# Wheel_Encoder_Adapter_Schmitt_555.net
KiCad netlist of a schematic drawn in EAGLE
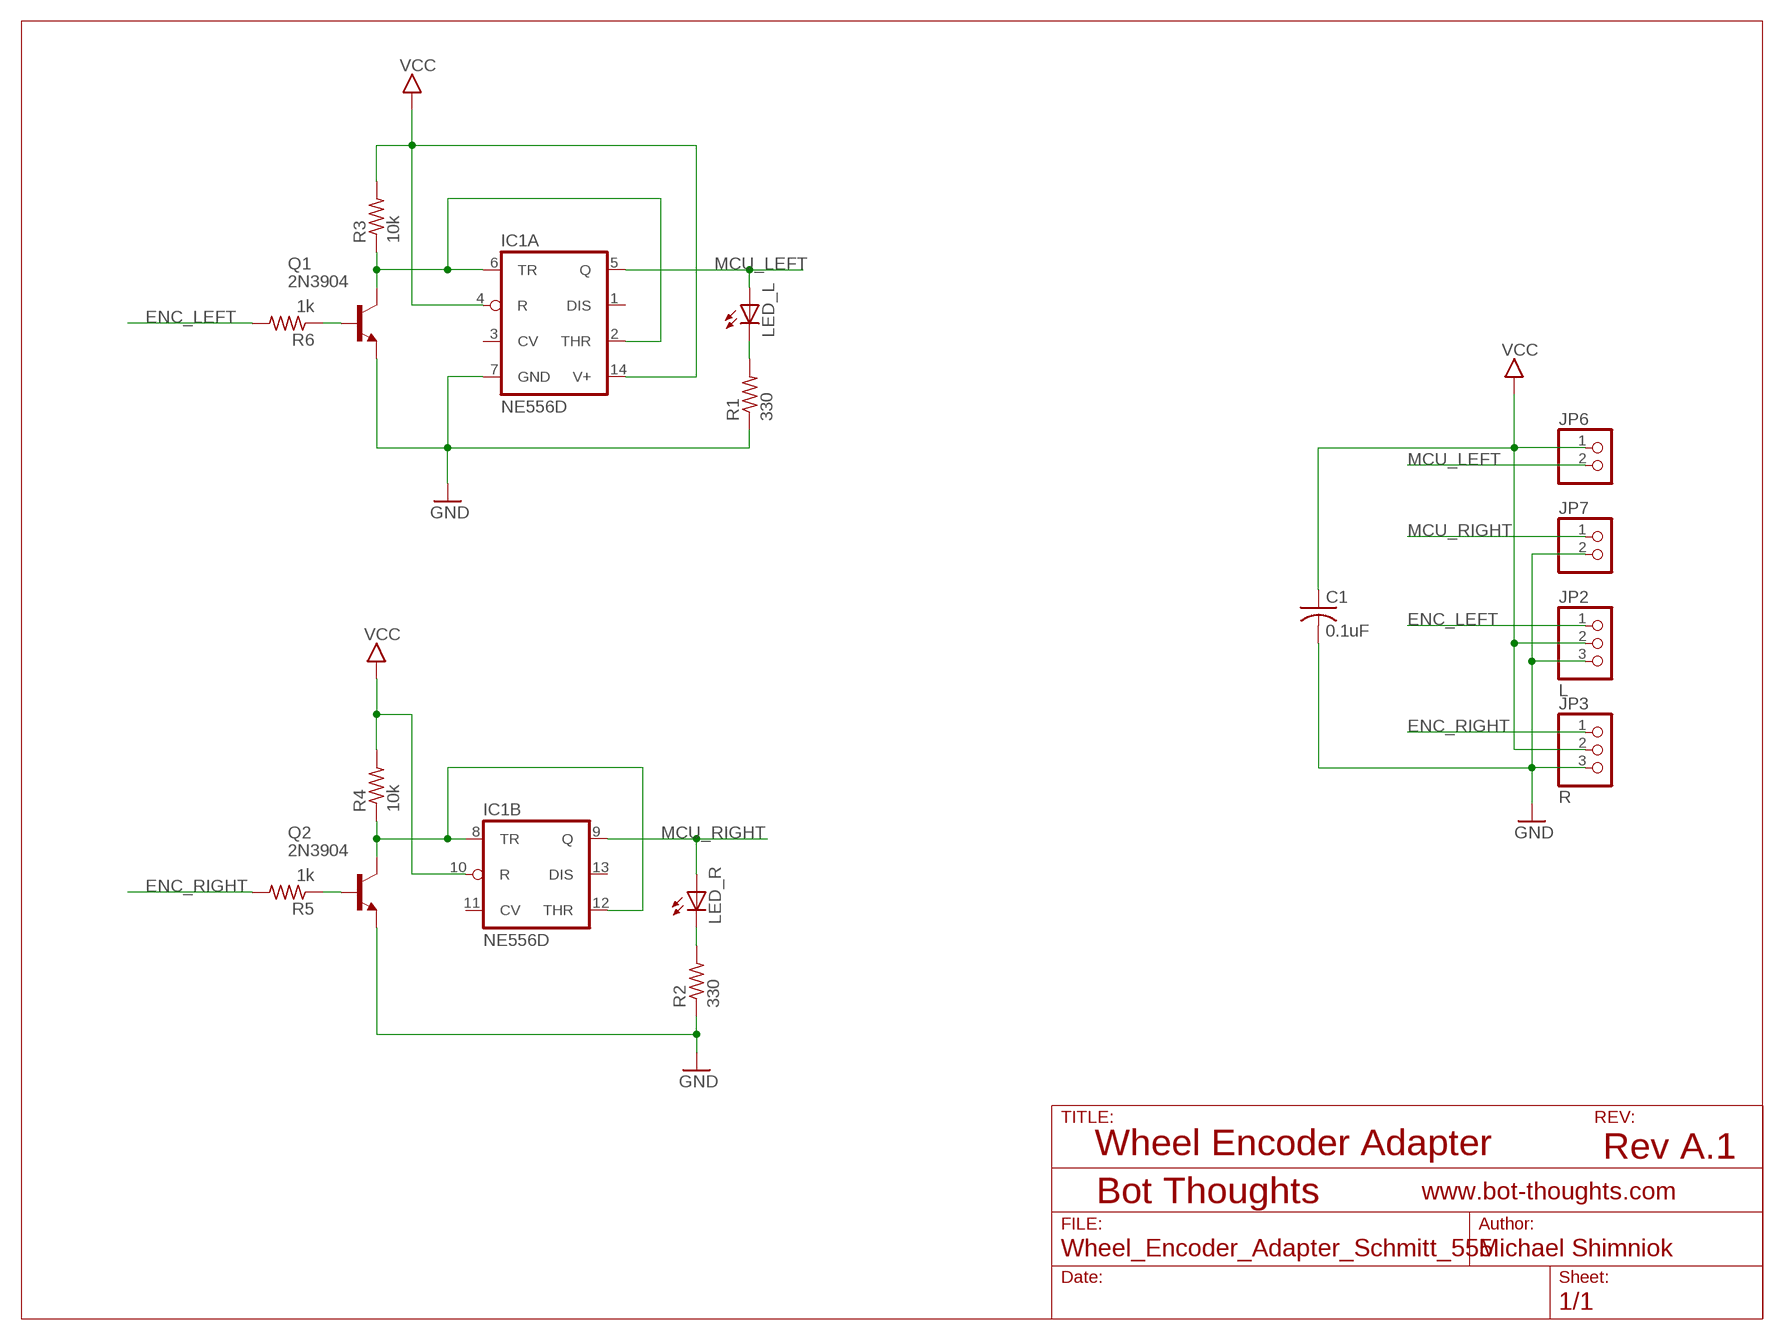
[diagram p0: schematic, sheet 1]

(export (version "E")
  (design (tool "Eeschema 10.0.6"))
  (components
    (comp (ref "C1")
      (value "0.1uF")
      (footprint "eagle-import:C0603")
      (libsource (lib "eagle-import") (part "C-USC0603"))
    )
    (comp (ref "IC1")
      (value "NE556D")
      (footprint "eagle-import:SO14")
      (libsource (lib "eagle-import") (part "556DNE"))
    )
    (comp (ref "JP2")
      (value "L")
      (footprint "eagle-import:1X03-S")
      (libsource (lib "eagle-import") (part "PINHD-1X03_2.54-S"))
    )
    (comp (ref "JP3")
      (value "R")
      (footprint "eagle-import:1X03-S")
      (libsource (lib "eagle-import") (part "PINHD-1X03_2.54-S"))
    )
    (comp (ref "JP6")
      (value "PINHD-1X02_2.54-S")
      (footprint "eagle-import:1X02-S")
      (libsource (lib "eagle-import") (part "PINHD-1X02_2.54-S"))
    )
    (comp (ref "JP7")
      (value "PINHD-1X02_2.54-S")
      (footprint "eagle-import:1X02-S")
      (libsource (lib "eagle-import") (part "PINHD-1X02_2.54-S"))
    )
    (comp (ref "LED_L")
      (value "LEDCHIPLED_0805")
      (footprint "eagle-import:CHIPLED_0805")
      (libsource (lib "eagle-import") (part "LEDCHIPLED_0805"))
    )
    (comp (ref "LED_R")
      (value "LEDCHIPLED_0805")
      (footprint "eagle-import:CHIPLED_0805")
      (libsource (lib "eagle-import") (part "LEDCHIPLED_0805"))
    )
    (comp (ref "Q1")
      (value "2N3904")
      (footprint "eagle-import:SOT-23")
      (libsource (lib "eagle-import") (part "2N3904SMD"))
    )
    (comp (ref "Q2")
      (value "2N3904")
      (footprint "eagle-import:SOT-23")
      (libsource (lib "eagle-import") (part "2N3904SMD"))
    )
    (comp (ref "R1")
      (value "330")
      (footprint "eagle-import:R0603")
      (libsource (lib "eagle-import") (part "R-US_R0603"))
    )
    (comp (ref "R2")
      (value "330")
      (footprint "eagle-import:R0603")
      (libsource (lib "eagle-import") (part "R-US_R0603"))
    )
    (comp (ref "R3")
      (value "10k")
      (footprint "eagle-import:R0603")
      (libsource (lib "eagle-import") (part "R-US_R0603"))
    )
    (comp (ref "R4")
      (value "10k")
      (footprint "eagle-import:R0603")
      (libsource (lib "eagle-import") (part "R-US_R0603"))
    )
    (comp (ref "R5")
      (value "1k")
      (footprint "eagle-import:R0603")
      (libsource (lib "eagle-import") (part "R-US_R0603"))
    )
    (comp (ref "R6")
      (value "1k")
      (footprint "eagle-import:R0603")
      (libsource (lib "eagle-import") (part "R-US_R0603"))
    )
  )
  (nets
    (net (code "1") (name "/ENC_LEFT") (class "Default")
      (node (ref "JP2") (pin "1") (pinfunction "1_1") (pintype "passive"))
      (node (ref "R6") (pin "2") (pinfunction "2_2") (pintype "passive"))
    )
    (net (code "2") (name "/ENC_RIGHT") (class "Default")
      (node (ref "JP3") (pin "1") (pinfunction "1_1") (pintype "passive"))
      (node (ref "R5") (pin "2") (pinfunction "2_2") (pintype "passive"))
    )
    (net (code "3") (name "/MCU_LEFT") (class "Default")
      (node (ref "IC1") (pin "5") (pinfunction "Q_5") (pintype "output"))
      (node (ref "JP6") (pin "2") (pinfunction "2_2") (pintype "passive"))
      (node (ref "LED_L") (pin "A") (pinfunction "A_A") (pintype "passive"))
    )
    (net (code "4") (name "/MCU_RIGHT") (class "Default")
      (node (ref "IC1") (pin "9") (pinfunction "Q_9") (pintype "output"))
      (node (ref "JP7") (pin "1") (pinfunction "1_1") (pintype "passive"))
      (node (ref "LED_R") (pin "A") (pinfunction "A_A") (pintype "passive"))
    )
    (net (code "5") (name "GND") (class "Default")
      (node (ref "C1") (pin "2") (pinfunction "2_2") (pintype "passive"))
      (node (ref "IC1") (pin "7") (pinfunction "GND_7") (pintype "power_in"))
      (node (ref "JP2") (pin "3") (pinfunction "3_3") (pintype "passive"))
      (node (ref "JP3") (pin "3") (pinfunction "3_3") (pintype "passive"))
      (node (ref "JP7") (pin "2") (pinfunction "2_2") (pintype "passive"))
      (node (ref "Q1") (pin "2") (pinfunction "E_2") (pintype "passive"))
      (node (ref "Q2") (pin "2") (pinfunction "E_2") (pintype "passive"))
      (node (ref "R1") (pin "1") (pinfunction "1_1") (pintype "passive"))
      (node (ref "R2") (pin "1") (pinfunction "1_1") (pintype "passive"))
    )
    (net (code "6") (name "Net-(IC1A-THR)") (class "Default")
      (node (ref "IC1") (pin "2") (pinfunction "THR_2") (pintype "input"))
      (node (ref "IC1") (pin "6") (pinfunction "TR_6") (pintype "input"))
      (node (ref "Q1") (pin "1") (pinfunction "C_1") (pintype "passive"))
      (node (ref "R3") (pin "1") (pinfunction "1_1") (pintype "passive"))
    )
    (net (code "7") (name "Net-(IC1B-THR)") (class "Default")
      (node (ref "IC1") (pin "12") (pinfunction "THR_12") (pintype "input"))
      (node (ref "IC1") (pin "8") (pinfunction "TR_8") (pintype "input"))
      (node (ref "Q2") (pin "1") (pinfunction "C_1") (pintype "passive"))
      (node (ref "R4") (pin "1") (pinfunction "1_1") (pintype "passive"))
    )
    (net (code "8") (name "Net-(LED_L-PadC)") (class "Default")
      (node (ref "LED_L") (pin "C") (pinfunction "C_C") (pintype "passive"))
      (node (ref "R1") (pin "2") (pinfunction "2_2") (pintype "passive"))
    )
    (net (code "9") (name "Net-(LED_R-PadC)") (class "Default")
      (node (ref "LED_R") (pin "C") (pinfunction "C_C") (pintype "passive"))
      (node (ref "R2") (pin "2") (pinfunction "2_2") (pintype "passive"))
    )
    (net (code "10") (name "Net-(Q1-B)") (class "Default")
      (node (ref "Q1") (pin "3") (pinfunction "B_3") (pintype "passive"))
      (node (ref "R6") (pin "1") (pinfunction "1_1") (pintype "passive"))
    )
    (net (code "11") (name "Net-(Q2-B)") (class "Default")
      (node (ref "Q2") (pin "3") (pinfunction "B_3") (pintype "passive"))
      (node (ref "R5") (pin "1") (pinfunction "1_1") (pintype "passive"))
    )
    (net (code "12") (name "VCC") (class "Default")
      (node (ref "C1") (pin "1") (pinfunction "1_1") (pintype "passive"))
      (node (ref "IC1") (pin "10") (pinfunction "R_10") (pintype "input"))
      (node (ref "IC1") (pin "14") (pinfunction "V+_14") (pintype "power_in"))
      (node (ref "IC1") (pin "4") (pinfunction "R_4") (pintype "input"))
      (node (ref "JP2") (pin "2") (pinfunction "2_2") (pintype "passive"))
      (node (ref "JP3") (pin "2") (pinfunction "2_2") (pintype "passive"))
      (node (ref "JP6") (pin "1") (pinfunction "1_1") (pintype "passive"))
      (node (ref "R3") (pin "2") (pinfunction "2_2") (pintype "passive"))
      (node (ref "R4") (pin "2") (pinfunction "2_2") (pintype "passive"))
    )
    (net (code "13") (name "unconnected-(IC1A-CV-Pad3)") (class "Default")
      (node (ref "IC1") (pin "3") (pinfunction "CV_3") (pintype "input"))
    )
    (net (code "14") (name "unconnected-(IC1A-DIS-Pad1)") (class "Default")
      (node (ref "IC1") (pin "1") (pinfunction "DIS_1") (pintype "input"))
    )
    (net (code "15") (name "unconnected-(IC1B-CV-Pad11)") (class "Default")
      (node (ref "IC1") (pin "11") (pinfunction "CV_11") (pintype "input"))
    )
    (net (code "16") (name "unconnected-(IC1B-DIS-Pad13)") (class "Default")
      (node (ref "IC1") (pin "13") (pinfunction "DIS_13") (pintype "input"))
    )
  )
)
